# J4.net
KiCad netlist of a schematic drawn in Altium Designer
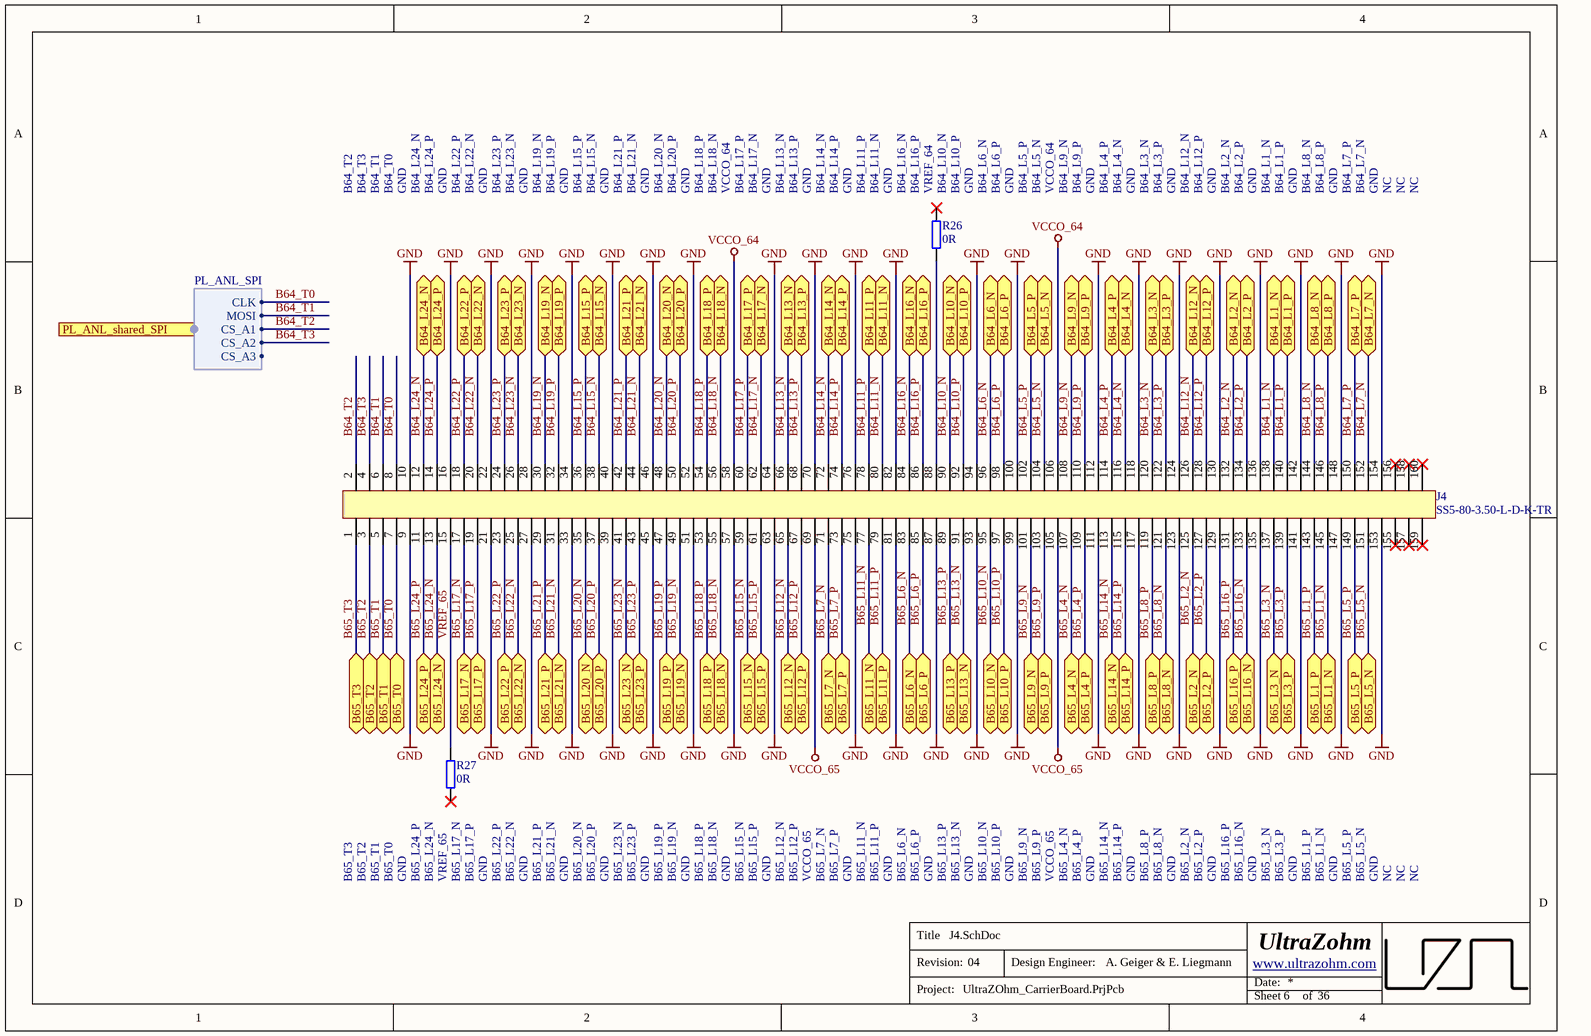
[diagram p0: J4.SchDoc]

(export (version "E")
  (design (tool "Eeschema 10.0.6"))
  (components
    (comp (ref "J4")
      (value "SS5-80-3.50-L-D-K-TR")
      (footprint "SS5-80-3.50-L-D-K-TR")
      (description "0.5 mm Ultra Fine Pitch Socket REF192552-01, 160 Pins")
      (fields
        (field (name "MANUFACTURER") "SAMTEC")
        (field (name "LCSC PART NUMBER") "C5292077")
        (field (name "CREATED FROM") "MGremer")
      )
      (libsource (lib "user") (part "SS5-80-3.50-L-D-K-TR"))
    )
    (comp (ref "R26")
      (value "0R")
      (footprint "R_0603_TE")
      (description "Generic resistor")
      (fields
        (field (name "TOLERANCE") "1 %")
        (field (name "MANUFACTURER PART NUMBER") "UZgen_R_0603_0R")
        (field (name "CREATED FROM") "UZgenTool")
      )
      (libsource (lib "user") (part "RES"))
    )
    (comp (ref "R27")
      (value "0R")
      (footprint "R_0603_TE")
      (description "Generic resistor")
      (fields
        (field (name "TOLERANCE") "1 %")
        (field (name "MANUFACTURER PART NUMBER") "UZgen_R_0603_0R")
        (field (name "CREATED FROM") "UZgenTool")
      )
      (libsource (lib "user") (part "RES"))
    )
  )
  (nets
    (net (code "2") (name "/B64_L1_N") (class "Default")
      (node (ref "J4") (pin "138") (pinfunction "138_138") (pintype "passive"))
    )
    (net (code "3") (name "/B64_L1_P") (class "Default")
      (node (ref "J4") (pin "140") (pinfunction "140_140") (pintype "passive"))
    )
    (net (code "4") (name "/B64_L2_N") (class "Default")
      (node (ref "J4") (pin "132") (pinfunction "132_132") (pintype "passive"))
    )
    (net (code "5") (name "/B64_L2_P") (class "Default")
      (node (ref "J4") (pin "134") (pinfunction "134_134") (pintype "passive"))
    )
    (net (code "6") (name "/B64_L3_N") (class "Default")
      (node (ref "J4") (pin "120") (pinfunction "120_120") (pintype "passive"))
    )
    (net (code "7") (name "/B64_L3_P") (class "Default")
      (node (ref "J4") (pin "122") (pinfunction "122_122") (pintype "passive"))
    )
    (net (code "8") (name "/B64_L4_N") (class "Default")
      (node (ref "J4") (pin "116") (pinfunction "116_116") (pintype "passive"))
    )
    (net (code "9") (name "/B64_L4_P") (class "Default")
      (node (ref "J4") (pin "114") (pinfunction "114_114") (pintype "passive"))
    )
    (net (code "10") (name "/B64_L5_N") (class "Default")
      (node (ref "J4") (pin "104") (pinfunction "104_104") (pintype "passive"))
    )
    (net (code "11") (name "/B64_L5_P") (class "Default")
      (node (ref "J4") (pin "102") (pinfunction "102_102") (pintype "passive"))
    )
    (net (code "12") (name "/B64_L6_N") (class "Default")
      (node (ref "J4") (pin "96") (pinfunction "96_96") (pintype "passive"))
    )
    (net (code "13") (name "/B64_L6_P") (class "Default")
      (node (ref "J4") (pin "98") (pinfunction "98_98") (pintype "passive"))
    )
    (net (code "14") (name "/B64_L7_N") (class "Default")
      (node (ref "J4") (pin "152") (pinfunction "152_152") (pintype "passive"))
    )
    (net (code "15") (name "/B64_L7_P") (class "Default")
      (node (ref "J4") (pin "150") (pinfunction "150_150") (pintype "passive"))
    )
    (net (code "16") (name "/B64_L8_N") (class "Default")
      (node (ref "J4") (pin "144") (pinfunction "144_144") (pintype "passive"))
    )
    (net (code "17") (name "/B64_L8_P") (class "Default")
      (node (ref "J4") (pin "146") (pinfunction "146_146") (pintype "passive"))
    )
    (net (code "18") (name "/B64_L9_N") (class "Default")
      (node (ref "J4") (pin "108") (pinfunction "108_108") (pintype "passive"))
    )
    (net (code "19") (name "/B64_L9_P") (class "Default")
      (node (ref "J4") (pin "110") (pinfunction "110_110") (pintype "passive"))
    )
    (net (code "20") (name "/B64_L10_N") (class "Default")
      (node (ref "J4") (pin "90") (pinfunction "90_90") (pintype "passive"))
    )
    (net (code "21") (name "/B64_L10_P") (class "Default")
      (node (ref "J4") (pin "92") (pinfunction "92_92") (pintype "passive"))
    )
    (net (code "22") (name "/B64_L11_N") (class "Default")
      (node (ref "J4") (pin "80") (pinfunction "80_80") (pintype "passive"))
    )
    (net (code "23") (name "/B64_L11_P") (class "Default")
      (node (ref "J4") (pin "78") (pinfunction "78_78") (pintype "passive"))
    )
    (net (code "24") (name "/B64_L12_N") (class "Default")
      (node (ref "J4") (pin "126") (pinfunction "126_126") (pintype "passive"))
    )
    (net (code "25") (name "/B64_L12_P") (class "Default")
      (node (ref "J4") (pin "128") (pinfunction "128_128") (pintype "passive"))
    )
    (net (code "26") (name "/B64_L13_N") (class "Default")
      (node (ref "J4") (pin "66") (pinfunction "66_66") (pintype "passive"))
    )
    (net (code "27") (name "/B64_L13_P") (class "Default")
      (node (ref "J4") (pin "68") (pinfunction "68_68") (pintype "passive"))
    )
    (net (code "28") (name "/B64_L14_N") (class "Default")
      (node (ref "J4") (pin "72") (pinfunction "72_72") (pintype "passive"))
    )
    (net (code "29") (name "/B64_L14_P") (class "Default")
      (node (ref "J4") (pin "74") (pinfunction "74_74") (pintype "passive"))
    )
    (net (code "30") (name "/B64_L15_N") (class "Default")
      (node (ref "J4") (pin "38") (pinfunction "38_38") (pintype "passive"))
    )
    (net (code "31") (name "/B64_L15_P") (class "Default")
      (node (ref "J4") (pin "36") (pinfunction "36_36") (pintype "passive"))
    )
    (net (code "32") (name "/B64_L16_N") (class "Default")
      (node (ref "J4") (pin "84") (pinfunction "84_84") (pintype "passive"))
    )
    (net (code "33") (name "/B64_L16_P") (class "Default")
      (node (ref "J4") (pin "86") (pinfunction "86_86") (pintype "passive"))
    )
    (net (code "34") (name "/B64_L17_N") (class "Default")
      (node (ref "J4") (pin "62") (pinfunction "62_62") (pintype "passive"))
    )
    (net (code "35") (name "/B64_L17_P") (class "Default")
      (node (ref "J4") (pin "60") (pinfunction "60_60") (pintype "passive"))
    )
    (net (code "36") (name "/B64_L18_N") (class "Default")
      (node (ref "J4") (pin "56") (pinfunction "56_56") (pintype "passive"))
    )
    (net (code "37") (name "/B64_L18_P") (class "Default")
      (node (ref "J4") (pin "54") (pinfunction "54_54") (pintype "passive"))
    )
    (net (code "38") (name "/B64_L19_N") (class "Default")
      (node (ref "J4") (pin "30") (pinfunction "30_30") (pintype "passive"))
    )
    (net (code "39") (name "/B64_L19_P") (class "Default")
      (node (ref "J4") (pin "32") (pinfunction "32_32") (pintype "passive"))
    )
    (net (code "40") (name "/B64_L20_N") (class "Default")
      (node (ref "J4") (pin "48") (pinfunction "48_48") (pintype "passive"))
    )
    (net (code "41") (name "/B64_L20_P") (class "Default")
      (node (ref "J4") (pin "50") (pinfunction "50_50") (pintype "passive"))
    )
    (net (code "42") (name "/B64_L21_N") (class "Default")
      (node (ref "J4") (pin "44") (pinfunction "44_44") (pintype "passive"))
    )
    (net (code "43") (name "/B64_L21_P") (class "Default")
      (node (ref "J4") (pin "42") (pinfunction "42_42") (pintype "passive"))
    )
    (net (code "44") (name "/B64_L22_N") (class "Default")
      (node (ref "J4") (pin "20") (pinfunction "20_20") (pintype "passive"))
    )
    (net (code "45") (name "/B64_L22_P") (class "Default")
      (node (ref "J4") (pin "18") (pinfunction "18_18") (pintype "passive"))
    )
    (net (code "46") (name "/B64_L23_N") (class "Default")
      (node (ref "J4") (pin "26") (pinfunction "26_26") (pintype "passive"))
    )
    (net (code "47") (name "/B64_L23_P") (class "Default")
      (node (ref "J4") (pin "24") (pinfunction "24_24") (pintype "passive"))
    )
    (net (code "48") (name "/B64_L24_N") (class "Default")
      (node (ref "J4") (pin "12") (pinfunction "12_12") (pintype "passive"))
    )
    (net (code "49") (name "/B64_L24_P") (class "Default")
      (node (ref "J4") (pin "14") (pinfunction "14_14") (pintype "passive"))
    )
    (net (code "50") (name "/B64_T0") (class "Default")
      (node (ref "J4") (pin "8") (pinfunction "8_8") (pintype "passive"))
    )
    (net (code "51") (name "/B64_T1") (class "Default")
      (node (ref "J4") (pin "6") (pinfunction "6_6") (pintype "passive"))
    )
    (net (code "52") (name "/B64_T2") (class "Default")
      (node (ref "J4") (pin "2") (pinfunction "2_2") (pintype "passive"))
    )
    (net (code "53") (name "/B64_T3") (class "Default")
      (node (ref "J4") (pin "4") (pinfunction "4_4") (pintype "passive"))
    )
    (net (code "54") (name "/B65_L1_N") (class "Default")
      (node (ref "J4") (pin "145") (pinfunction "145_145") (pintype "passive"))
    )
    (net (code "55") (name "/B65_L1_P") (class "Default")
      (node (ref "J4") (pin "143") (pinfunction "143_143") (pintype "passive"))
    )
    (net (code "56") (name "/B65_L2_N") (class "Default")
      (node (ref "J4") (pin "125") (pinfunction "125_125") (pintype "passive"))
    )
    (net (code "57") (name "/B65_L2_P") (class "Default")
      (node (ref "J4") (pin "127") (pinfunction "127_127") (pintype "passive"))
    )
    (net (code "58") (name "/B65_L3_N") (class "Default")
      (node (ref "J4") (pin "137") (pinfunction "137_137") (pintype "passive"))
    )
    (net (code "59") (name "/B65_L3_P") (class "Default")
      (node (ref "J4") (pin "139") (pinfunction "139_139") (pintype "passive"))
    )
    (net (code "60") (name "/B65_L4_N") (class "Default")
      (node (ref "J4") (pin "107") (pinfunction "107_107") (pintype "passive"))
    )
    (net (code "61") (name "/B65_L4_P") (class "Default")
      (node (ref "J4") (pin "109") (pinfunction "109_109") (pintype "passive"))
    )
    (net (code "62") (name "/B65_L5_N") (class "Default")
      (node (ref "J4") (pin "151") (pinfunction "151_151") (pintype "passive"))
    )
    (net (code "63") (name "/B65_L5_P") (class "Default")
      (node (ref "J4") (pin "149") (pinfunction "149_149") (pintype "passive"))
    )
    (net (code "64") (name "/B65_L6_N") (class "Default")
      (node (ref "J4") (pin "83") (pinfunction "83_83") (pintype "passive"))
    )
    (net (code "65") (name "/B65_L6_P") (class "Default")
      (node (ref "J4") (pin "85") (pinfunction "85_85") (pintype "passive"))
    )
    (net (code "66") (name "/B65_L7_N") (class "Default")
      (node (ref "J4") (pin "71") (pinfunction "71_71") (pintype "passive"))
    )
    (net (code "67") (name "/B65_L7_P") (class "Default")
      (node (ref "J4") (pin "73") (pinfunction "73_73") (pintype "passive"))
    )
    (net (code "68") (name "/B65_L8_N") (class "Default")
      (node (ref "J4") (pin "121") (pinfunction "121_121") (pintype "passive"))
    )
    (net (code "69") (name "/B65_L8_P") (class "Default")
      (node (ref "J4") (pin "119") (pinfunction "119_119") (pintype "passive"))
    )
    (net (code "70") (name "/B65_L9_N") (class "Default")
      (node (ref "J4") (pin "101") (pinfunction "101_101") (pintype "passive"))
    )
    (net (code "71") (name "/B65_L9_P") (class "Default")
      (node (ref "J4") (pin "103") (pinfunction "103_103") (pintype "passive"))
    )
    (net (code "72") (name "/B65_L10_N") (class "Default")
      (node (ref "J4") (pin "95") (pinfunction "95_95") (pintype "passive"))
    )
    (net (code "73") (name "/B65_L10_P") (class "Default")
      (node (ref "J4") (pin "97") (pinfunction "97_97") (pintype "passive"))
    )
    (net (code "74") (name "/B65_L11_N") (class "Default")
      (node (ref "J4") (pin "77") (pinfunction "77_77") (pintype "passive"))
    )
    (net (code "75") (name "/B65_L11_P") (class "Default")
      (node (ref "J4") (pin "79") (pinfunction "79_79") (pintype "passive"))
    )
    (net (code "76") (name "/B65_L12_N") (class "Default")
      (node (ref "J4") (pin "65") (pinfunction "65_65") (pintype "passive"))
    )
    (net (code "77") (name "/B65_L12_P") (class "Default")
      (node (ref "J4") (pin "67") (pinfunction "67_67") (pintype "passive"))
    )
    (net (code "78") (name "/B65_L13_N") (class "Default")
      (node (ref "J4") (pin "91") (pinfunction "91_91") (pintype "passive"))
    )
    (net (code "79") (name "/B65_L13_P") (class "Default")
      (node (ref "J4") (pin "89") (pinfunction "89_89") (pintype "passive"))
    )
    (net (code "80") (name "/B65_L14_N") (class "Default")
      (node (ref "J4") (pin "113") (pinfunction "113_113") (pintype "passive"))
    )
    (net (code "81") (name "/B65_L14_P") (class "Default")
      (node (ref "J4") (pin "115") (pinfunction "115_115") (pintype "passive"))
    )
    (net (code "82") (name "/B65_L15_N") (class "Default")
      (node (ref "J4") (pin "59") (pinfunction "59_59") (pintype "passive"))
    )
    (net (code "83") (name "/B65_L15_P") (class "Default")
      (node (ref "J4") (pin "61") (pinfunction "61_61") (pintype "passive"))
    )
    (net (code "84") (name "/B65_L16_N") (class "Default")
      (node (ref "J4") (pin "133") (pinfunction "133_133") (pintype "passive"))
    )
    (net (code "85") (name "/B65_L16_P") (class "Default")
      (node (ref "J4") (pin "131") (pinfunction "131_131") (pintype "passive"))
    )
    (net (code "86") (name "/B65_L17_N") (class "Default")
      (node (ref "J4") (pin "17") (pinfunction "17_17") (pintype "passive"))
    )
    (net (code "87") (name "/B65_L17_P") (class "Default")
      (node (ref "J4") (pin "19") (pinfunction "19_19") (pintype "passive"))
    )
    (net (code "88") (name "/B65_L18_N") (class "Default")
      (node (ref "J4") (pin "55") (pinfunction "55_55") (pintype "passive"))
    )
    (net (code "89") (name "/B65_L18_P") (class "Default")
      (node (ref "J4") (pin "53") (pinfunction "53_53") (pintype "passive"))
    )
    (net (code "90") (name "/B65_L19_N") (class "Default")
      (node (ref "J4") (pin "49") (pinfunction "49_49") (pintype "passive"))
    )
    (net (code "91") (name "/B65_L19_P") (class "Default")
      (node (ref "J4") (pin "47") (pinfunction "47_47") (pintype "passive"))
    )
    (net (code "92") (name "/B65_L20_N") (class "Default")
      (node (ref "J4") (pin "35") (pinfunction "35_35") (pintype "passive"))
    )
    (net (code "93") (name "/B65_L20_P") (class "Default")
      (node (ref "J4") (pin "37") (pinfunction "37_37") (pintype "passive"))
    )
    (net (code "94") (name "/B65_L21_N") (class "Default")
      (node (ref "J4") (pin "31") (pinfunction "31_31") (pintype "passive"))
    )
    (net (code "95") (name "/B65_L21_P") (class "Default")
      (node (ref "J4") (pin "29") (pinfunction "29_29") (pintype "passive"))
    )
    (net (code "96") (name "/B65_L22_N") (class "Default")
      (node (ref "J4") (pin "25") (pinfunction "25_25") (pintype "passive"))
    )
    (net (code "97") (name "/B65_L22_P") (class "Default")
      (node (ref "J4") (pin "23") (pinfunction "23_23") (pintype "passive"))
    )
    (net (code "98") (name "/B65_L23_N") (class "Default")
      (node (ref "J4") (pin "41") (pinfunction "41_41") (pintype "passive"))
    )
    (net (code "99") (name "/B65_L23_P") (class "Default")
      (node (ref "J4") (pin "43") (pinfunction "43_43") (pintype "passive"))
    )
    (net (code "100") (name "/B65_L24_N") (class "Default")
      (node (ref "J4") (pin "13") (pinfunction "13_13") (pintype "passive"))
    )
    (net (code "101") (name "/B65_L24_P") (class "Default")
      (node (ref "J4") (pin "11") (pinfunction "11_11") (pintype "passive"))
    )
    (net (code "102") (name "/B65_T0") (class "Default")
      (node (ref "J4") (pin "7") (pinfunction "7_7") (pintype "passive"))
    )
    (net (code "103") (name "/B65_T1") (class "Default")
      (node (ref "J4") (pin "5") (pinfunction "5_5") (pintype "passive"))
    )
    (net (code "104") (name "/B65_T2") (class "Default")
      (node (ref "J4") (pin "3") (pinfunction "3_3") (pintype "passive"))
    )
    (net (code "105") (name "/B65_T3") (class "Default")
      (node (ref "J4") (pin "1") (pinfunction "1_1") (pintype "passive"))
    )
    (net (code "106") (name "/VREF_65") (class "Default")
      (node (ref "J4") (pin "15") (pinfunction "15_15") (pintype "passive"))
      (node (ref "R27") (pin "2") (pinfunction "2_2") (pintype "passive"))
    )
    (net (code "108") (name "GND") (class "Default")
      (node (ref "J4") (pin "10") (pinfunction "10_10") (pintype "passive"))
      (node (ref "J4") (pin "100") (pinfunction "100_100") (pintype "passive"))
      (node (ref "J4") (pin "111") (pinfunction "111_111") (pintype "passive"))
      (node (ref "J4") (pin "112") (pinfunction "112_112") (pintype "passive"))
      (node (ref "J4") (pin "117") (pinfunction "117_117") (pintype "passive"))
      (node (ref "J4") (pin "118") (pinfunction "118_118") (pintype "passive"))
      (node (ref "J4") (pin "123") (pinfunction "123_123") (pintype "passive"))
      (node (ref "J4") (pin "124") (pinfunction "124_124") (pintype "passive"))
      (node (ref "J4") (pin "129") (pinfunction "129_129") (pintype "passive"))
      (node (ref "J4") (pin "130") (pinfunction "130_130") (pintype "passive"))
      (node (ref "J4") (pin "135") (pinfunction "135_135") (pintype "passive"))
      (node (ref "J4") (pin "136") (pinfunction "136_136") (pintype "passive"))
      (node (ref "J4") (pin "141") (pinfunction "141_141") (pintype "passive"))
      (node (ref "J4") (pin "142") (pinfunction "142_142") (pintype "passive"))
      (node (ref "J4") (pin "147") (pinfunction "147_147") (pintype "passive"))
      (node (ref "J4") (pin "148") (pinfunction "148_148") (pintype "passive"))
      (node (ref "J4") (pin "153") (pinfunction "153_153") (pintype "passive"))
      (node (ref "J4") (pin "154") (pinfunction "154_154") (pintype "passive"))
      (node (ref "J4") (pin "16") (pinfunction "16_16") (pintype "passive"))
      (node (ref "J4") (pin "21") (pinfunction "21_21") (pintype "passive"))
      (node (ref "J4") (pin "22") (pinfunction "22_22") (pintype "passive"))
      (node (ref "J4") (pin "27") (pinfunction "27_27") (pintype "passive"))
      (node (ref "J4") (pin "28") (pinfunction "28_28") (pintype "passive"))
      (node (ref "J4") (pin "33") (pinfunction "33_33") (pintype "passive"))
      (node (ref "J4") (pin "34") (pinfunction "34_34") (pintype "passive"))
      (node (ref "J4") (pin "39") (pinfunction "39_39") (pintype "passive"))
      (node (ref "J4") (pin "40") (pinfunction "40_40") (pintype "passive"))
      (node (ref "J4") (pin "45") (pinfunction "45_45") (pintype "passive"))
      (node (ref "J4") (pin "46") (pinfunction "46_46") (pintype "passive"))
      (node (ref "J4") (pin "51") (pinfunction "51_51") (pintype "passive"))
      (node (ref "J4") (pin "52") (pinfunction "52_52") (pintype "passive"))
      (node (ref "J4") (pin "57") (pinfunction "57_57") (pintype "passive"))
      (node (ref "J4") (pin "63") (pinfunction "63_63") (pintype "passive"))
      (node (ref "J4") (pin "64") (pinfunction "64_64") (pintype "passive"))
      (node (ref "J4") (pin "70") (pinfunction "70_70") (pintype "passive"))
      (node (ref "J4") (pin "75") (pinfunction "75_75") (pintype "passive"))
      (node (ref "J4") (pin "76") (pinfunction "76_76") (pintype "passive"))
      (node (ref "J4") (pin "81") (pinfunction "81_81") (pintype "passive"))
      (node (ref "J4") (pin "82") (pinfunction "82_82") (pintype "passive"))
      (node (ref "J4") (pin "87") (pinfunction "87_87") (pintype "passive"))
      (node (ref "J4") (pin "9") (pinfunction "9_9") (pintype "passive"))
      (node (ref "J4") (pin "93") (pinfunction "93_93") (pintype "passive"))
      (node (ref "J4") (pin "94") (pinfunction "94_94") (pintype "passive"))
      (node (ref "J4") (pin "99") (pinfunction "99_99") (pintype "passive"))
    )
    (net (code "109") (name "Net-(J4-Pad88)") (class "Default")
      (node (ref "J4") (pin "88") (pinfunction "88_88") (pintype "passive"))
      (node (ref "R26") (pin "1") (pinfunction "1_1") (pintype "passive"))
    )
    (net (code "110") (name "VCCO_64") (class "Default")
      (node (ref "J4") (pin "106") (pinfunction "106_106") (pintype "passive"))
      (node (ref "J4") (pin "58") (pinfunction "58_58") (pintype "passive"))
    )
    (net (code "111") (name "VCCO_65") (class "Default")
      (node (ref "J4") (pin "105") (pinfunction "105_105") (pintype "passive"))
      (node (ref "J4") (pin "69") (pinfunction "69_69") (pintype "passive"))
    )
    (net (code "112") (name "unconnected-(J4-Pad155)") (class "Default")
      (node (ref "J4") (pin "155") (pinfunction "155_155") (pintype "passive+no_connect"))
    )
    (net (code "113") (name "unconnected-(J4-Pad156)") (class "Default")
      (node (ref "J4") (pin "156") (pinfunction "156_156") (pintype "passive+no_connect"))
    )
    (net (code "114") (name "unconnected-(J4-Pad157)") (class "Default")
      (node (ref "J4") (pin "157") (pinfunction "157_157") (pintype "passive+no_connect"))
    )
    (net (code "115") (name "unconnected-(J4-Pad158)") (class "Default")
      (node (ref "J4") (pin "158") (pinfunction "158_158") (pintype "passive+no_connect"))
    )
    (net (code "116") (name "unconnected-(J4-Pad159)") (class "Default")
      (node (ref "J4") (pin "159") (pinfunction "159_159") (pintype "passive+no_connect"))
    )
    (net (code "117") (name "unconnected-(J4-Pad160)") (class "Default")
      (node (ref "J4") (pin "160") (pinfunction "160_160") (pintype "passive+no_connect"))
    )
    (net (code "118") (name "unconnected-(R26-Pad2)") (class "Default")
      (node (ref "R26") (pin "2") (pinfunction "2_2") (pintype "passive+no_connect"))
    )
    (net (code "119") (name "unconnected-(R27-Pad1)") (class "Default")
      (node (ref "R27") (pin "1") (pinfunction "1_1") (pintype "passive+no_connect"))
    )
  )
)
